# untitled.net
KiCad netlist of a schematic drawn in EAGLE
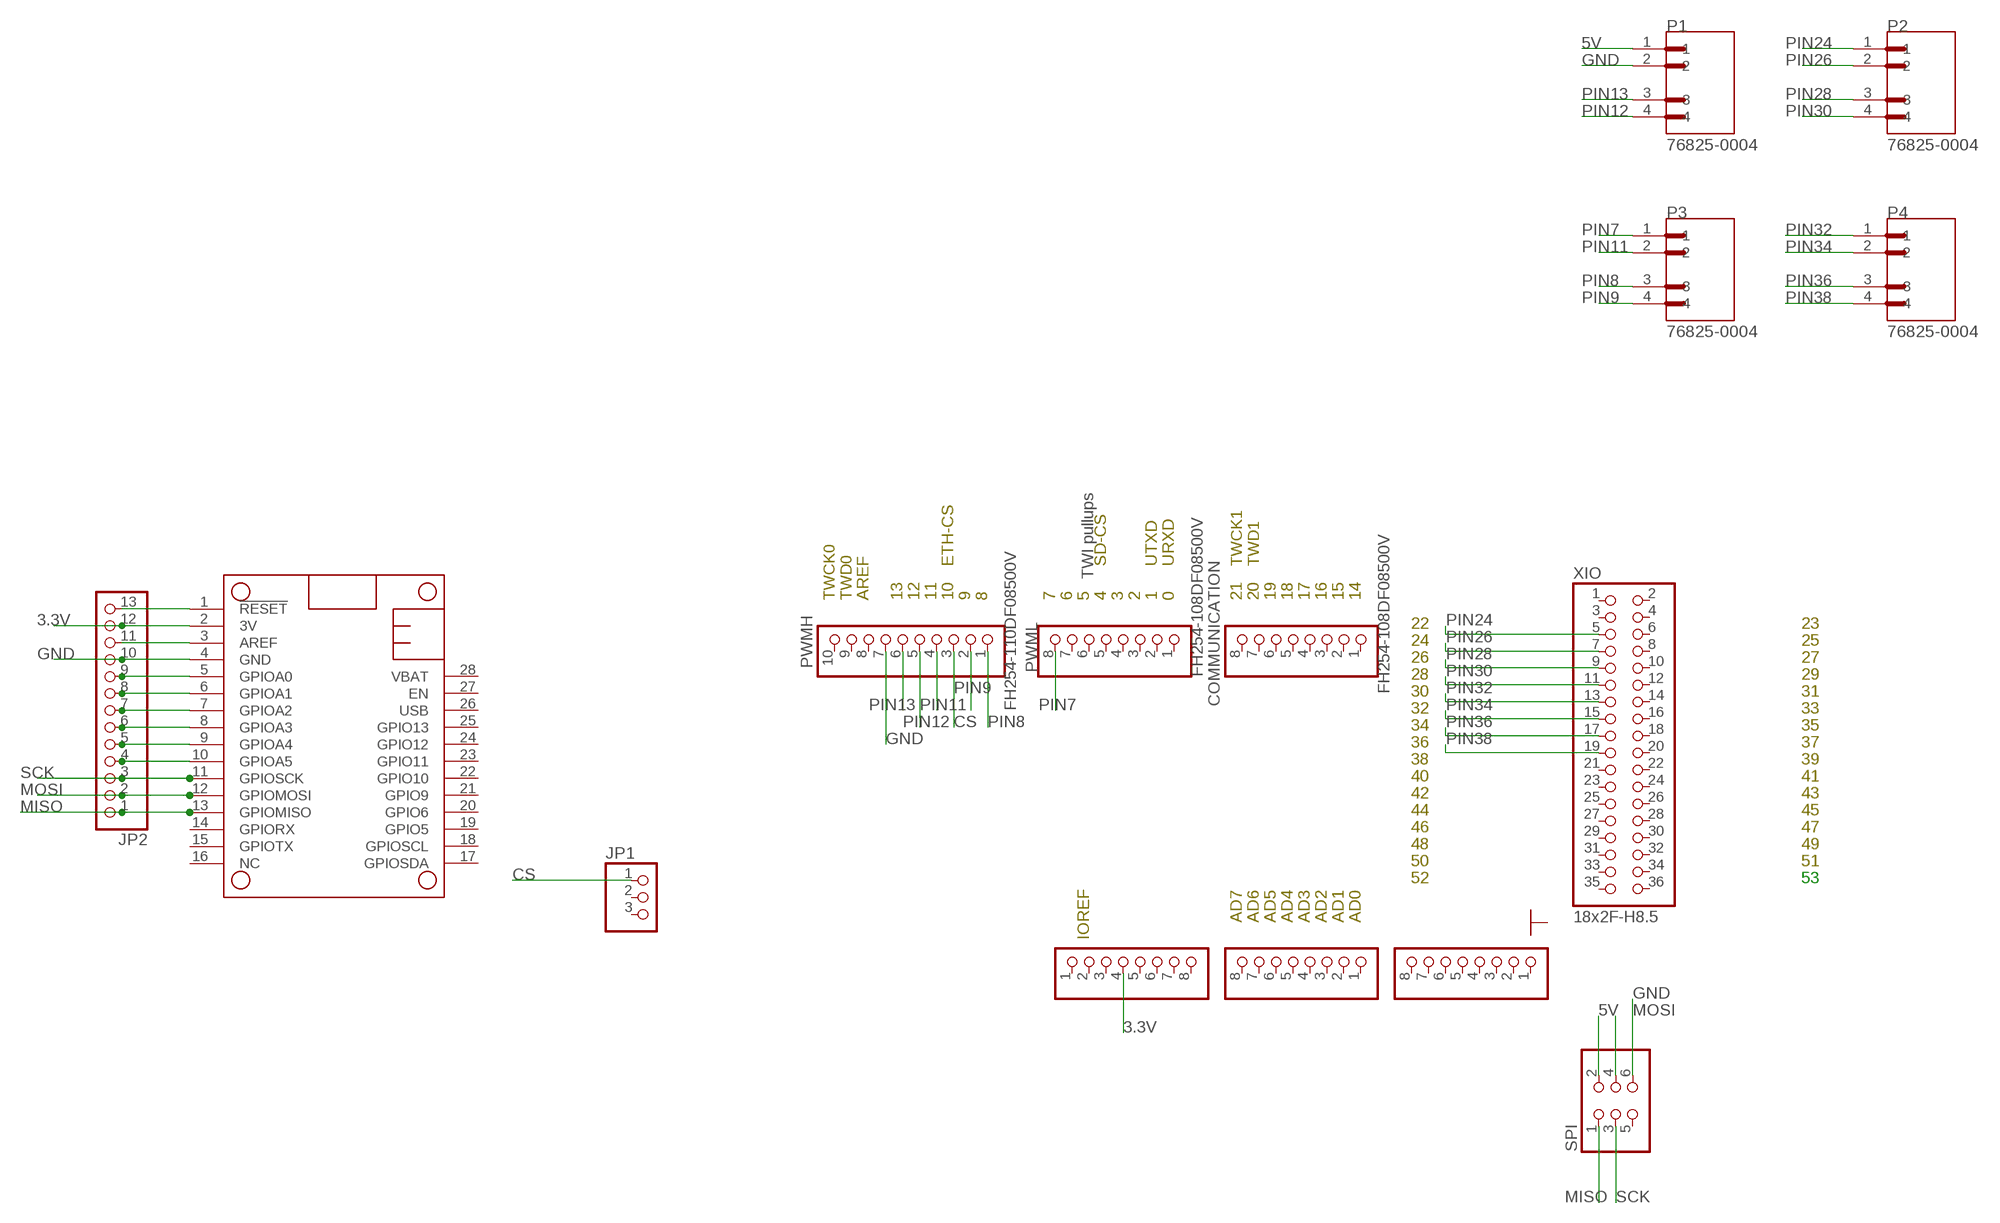
[diagram p0: schematic, sheet 1]

(export (version "E")
  (design (tool "Eeschema 10.0.6"))
  (components
    (comp (ref "ADCH")
      (value "FH254-108DF08500V")
      (footprint "eagle-import:1X08")
      (fields (field (name "PART_NUMBER") "20TW-536"))
      (libsource (lib "eagle-import") (part "1683_20TW-536"))
    )
    (comp (ref "ADCL")
      (value "FH254-108DF08500V")
      (footprint "eagle-import:1X08")
      (fields (field (name "PART_NUMBER") "20TW-536"))
      (libsource (lib "eagle-import") (part "1683_20TW-536"))
    )
    (comp (ref "COMMUNICATION")
      (value "FH254-108DF08500V")
      (footprint "eagle-import:1X08")
      (fields (field (name "PART_NUMBER") "20TW-536"))
      (libsource (lib "eagle-import") (part "1683_20TW-536"))
    )
    (comp (ref "JP1")
      (value "HEADER-1X376MIL")
      (footprint "eagle-import:1X03_ROUND_76")
      (libsource (lib "eagle-import") (part "HEADER-1X376MIL"))
    )
    (comp (ref "JP2")
      (value "HEADER-1X13")
      (footprint "eagle-import:1X13_ROUND_70")
      (libsource (lib "eagle-import") (part "HEADER-1X13"))
    )
    (comp (ref "MS1")
      (value "FEATHERWING_NODIM")
      (footprint "eagle-import:FEATHERWING_NODIM")
      (libsource (lib "eagle-import") (part "FEATHERWING_NODIM"))
    )
    (comp (ref "P1")
      (value "76825-0004")
      (footprint "eagle-import:MOLEX_76825-0004")
      (fields (field (name "MF") "Molex") (field (name "MP") "768250004"))
      (libsource (lib "eagle-import") (part "76825-0004"))
    )
    (comp (ref "P2")
      (value "76825-0004")
      (footprint "eagle-import:MOLEX_76825-0004")
      (fields (field (name "MF") "Molex") (field (name "MP") "768250004"))
      (libsource (lib "eagle-import") (part "76825-0004"))
    )
    (comp (ref "P3")
      (value "76825-0004")
      (footprint "eagle-import:MOLEX_76825-0004")
      (fields (field (name "MF") "Molex") (field (name "MP") "768250004"))
      (libsource (lib "eagle-import") (part "76825-0004"))
    )
    (comp (ref "P4")
      (value "76825-0004")
      (footprint "eagle-import:MOLEX_76825-0004")
      (fields (field (name "MF") "Molex") (field (name "MP") "768250004"))
      (libsource (lib "eagle-import") (part "76825-0004"))
    )
    (comp (ref "POWER")
      (value "FH254-108DF08500V")
      (footprint "eagle-import:1X08")
      (fields (field (name "PART_NUMBER") "20TW-536"))
      (libsource (lib "eagle-import") (part "1683_20TW-536"))
    )
    (comp (ref "PWMH")
      (value "FH254-110DF08500V")
      (footprint "eagle-import:1X10")
      (fields (field (name "PART_NUMBER") "20TW-537"))
      (libsource (lib "eagle-import") (part "1684_20TW-537"))
    )
    (comp (ref "PWML")
      (value "FH254-108DF08500V")
      (footprint "eagle-import:1X08")
      (fields (field (name "PART_NUMBER") "20TW-536"))
      (libsource (lib "eagle-import") (part "1683_20TW-536"))
    )
    (comp (ref "SPI")
      (value "ICSP")
      (footprint "eagle-import:2X03")
      (fields (field (name "PART_NUMBER") "PH254-203DF118A00V"))
      (libsource (lib "eagle-import") (part "0114_PH254-203DF118A00V"))
    )
    (comp (ref "XIO")
      (value "18x2F-H8.5")
      (footprint "eagle-import:2X18")
      (fields (field (name "PART_NUMBER") "12TW323"))
      (libsource (lib "eagle-import") (part "1756_12TW323"))
    )
  )
  (nets
    (net (code "1") (name "/3.3V") (class "Default")
      (node (ref "JP2") (pin "11") (pinfunction "11_11") (pintype "passive"))
      (node (ref "JP2") (pin "12") (pinfunction "12_12") (pintype "passive"))
      (node (ref "MS1") (pin "2") (pinfunction "3V_2") (pintype "power_in"))
      (node (ref "MS1") (pin "3") (pinfunction "AREF_3") (pintype "passive"))
      (node (ref "POWER") (pin "4") (pinfunction "4_4") (pintype "passive"))
    )
    (net (code "2") (name "/5V") (class "Default")
      (node (ref "P1") (pin "1") (pinfunction "1_1") (pintype "passive"))
      (node (ref "SPI") (pin "2") (pinfunction "2_2") (pintype "passive"))
    )
    (net (code "3") (name "/CS") (class "Default")
      (node (ref "JP1") (pin "1") (pinfunction "1_1") (pintype "passive"))
      (node (ref "PWMH") (pin "3") (pinfunction "3_3") (pintype "passive"))
    )
    (net (code "4") (name "/MISO") (class "Default")
      (node (ref "JP2") (pin "1") (pinfunction "1_1") (pintype "passive"))
      (node (ref "MS1") (pin "13") (pinfunction "GPIOMISO_13") (pintype "bidirectional"))
      (node (ref "SPI") (pin "1") (pinfunction "1_1") (pintype "passive"))
    )
    (net (code "5") (name "/MOSI") (class "Default")
      (node (ref "JP2") (pin "2") (pinfunction "2_2") (pintype "passive"))
      (node (ref "MS1") (pin "12") (pinfunction "GPIOMOSI_12") (pintype "bidirectional"))
      (node (ref "SPI") (pin "4") (pinfunction "4_4") (pintype "passive"))
    )
    (net (code "6") (name "/PIN7") (class "Default")
      (node (ref "P3") (pin "1") (pinfunction "1_1") (pintype "passive"))
      (node (ref "PWML") (pin "8") (pinfunction "8_8") (pintype "passive"))
    )
    (net (code "7") (name "/PIN8") (class "Default")
      (node (ref "P3") (pin "3") (pinfunction "3_3") (pintype "passive"))
      (node (ref "PWMH") (pin "1") (pinfunction "1_1") (pintype "passive"))
    )
    (net (code "8") (name "/PIN9") (class "Default")
      (node (ref "P3") (pin "4") (pinfunction "4_4") (pintype "passive"))
      (node (ref "PWMH") (pin "2") (pinfunction "2_2") (pintype "passive"))
    )
    (net (code "9") (name "/PIN11") (class "Default")
      (node (ref "P3") (pin "2") (pinfunction "2_2") (pintype "passive"))
      (node (ref "PWMH") (pin "4") (pinfunction "4_4") (pintype "passive"))
    )
    (net (code "10") (name "/PIN12") (class "Default")
      (node (ref "P1") (pin "4") (pinfunction "4_4") (pintype "passive"))
      (node (ref "PWMH") (pin "5") (pinfunction "5_5") (pintype "passive"))
    )
    (net (code "11") (name "/PIN13") (class "Default")
      (node (ref "P1") (pin "3") (pinfunction "3_3") (pintype "passive"))
      (node (ref "PWMH") (pin "6") (pinfunction "6_6") (pintype "passive"))
    )
    (net (code "12") (name "/PIN24") (class "Default")
      (node (ref "P2") (pin "1") (pinfunction "1_1") (pintype "passive"))
      (node (ref "XIO") (pin "5") (pinfunction "5_5") (pintype "passive"))
    )
    (net (code "13") (name "/PIN26") (class "Default")
      (node (ref "P2") (pin "2") (pinfunction "2_2") (pintype "passive"))
      (node (ref "XIO") (pin "7") (pinfunction "7_7") (pintype "passive"))
    )
    (net (code "14") (name "/PIN28") (class "Default")
      (node (ref "P2") (pin "3") (pinfunction "3_3") (pintype "passive"))
      (node (ref "XIO") (pin "9") (pinfunction "9_9") (pintype "passive"))
    )
    (net (code "15") (name "/PIN30") (class "Default")
      (node (ref "P2") (pin "4") (pinfunction "4_4") (pintype "passive"))
      (node (ref "XIO") (pin "11") (pinfunction "11_11") (pintype "passive"))
    )
    (net (code "16") (name "/PIN32") (class "Default")
      (node (ref "P4") (pin "1") (pinfunction "1_1") (pintype "passive"))
      (node (ref "XIO") (pin "13") (pinfunction "13_13") (pintype "passive"))
    )
    (net (code "17") (name "/PIN34") (class "Default")
      (node (ref "P4") (pin "2") (pinfunction "2_2") (pintype "passive"))
      (node (ref "XIO") (pin "15") (pinfunction "15_15") (pintype "passive"))
    )
    (net (code "18") (name "/PIN36") (class "Default")
      (node (ref "P4") (pin "3") (pinfunction "3_3") (pintype "passive"))
      (node (ref "XIO") (pin "17") (pinfunction "17_17") (pintype "passive"))
    )
    (net (code "19") (name "/PIN38") (class "Default")
      (node (ref "P4") (pin "4") (pinfunction "4_4") (pintype "passive"))
      (node (ref "XIO") (pin "19") (pinfunction "19_19") (pintype "passive"))
    )
    (net (code "20") (name "/SCK") (class "Default")
      (node (ref "JP2") (pin "3") (pinfunction "3_3") (pintype "passive"))
      (node (ref "MS1") (pin "11") (pinfunction "GPIOSCK_11") (pintype "bidirectional"))
      (node (ref "SPI") (pin "3") (pinfunction "3_3") (pintype "passive"))
    )
    (net (code "21") (name "/USB") (class "Default")
      (node (ref "MS1") (pin "26") (pinfunction "USB_26") (pintype "power_in"))
    )
    (net (code "22") (name "/VBAT") (class "Default")
      (node (ref "MS1") (pin "28") (pinfunction "VBAT_28") (pintype "power_in"))
    )
    (net (code "23") (name "GND") (class "Default")
      (node (ref "JP2") (pin "10") (pinfunction "10_10") (pintype "passive"))
      (node (ref "MS1") (pin "4") (pinfunction "GND_4") (pintype "power_in"))
      (node (ref "P1") (pin "2") (pinfunction "2_2") (pintype "passive"))
      (node (ref "PWMH") (pin "7") (pinfunction "7_7") (pintype "passive"))
      (node (ref "SPI") (pin "6") (pinfunction "6_6") (pintype "passive"))
    )
    (net (code "24") (name "Net-(MS1-GPIOA0)") (class "Default")
      (node (ref "JP2") (pin "9") (pinfunction "9_9") (pintype "passive"))
      (node (ref "MS1") (pin "5") (pinfunction "GPIOA0_5") (pintype "bidirectional"))
    )
    (net (code "25") (name "Net-(MS1-GPIOA1)") (class "Default")
      (node (ref "JP2") (pin "8") (pinfunction "8_8") (pintype "passive"))
      (node (ref "MS1") (pin "6") (pinfunction "GPIOA1_6") (pintype "bidirectional"))
    )
    (net (code "26") (name "Net-(MS1-GPIOA2)") (class "Default")
      (node (ref "JP2") (pin "7") (pinfunction "7_7") (pintype "passive"))
      (node (ref "MS1") (pin "7") (pinfunction "GPIOA2_7") (pintype "bidirectional"))
    )
    (net (code "27") (name "Net-(MS1-GPIOA3)") (class "Default")
      (node (ref "JP2") (pin "6") (pinfunction "6_6") (pintype "passive"))
      (node (ref "MS1") (pin "8") (pinfunction "GPIOA3_8") (pintype "bidirectional"))
    )
    (net (code "28") (name "Net-(MS1-GPIOA4)") (class "Default")
      (node (ref "JP2") (pin "5") (pinfunction "5_5") (pintype "passive"))
      (node (ref "MS1") (pin "9") (pinfunction "GPIOA4_9") (pintype "bidirectional"))
    )
    (net (code "29") (name "Net-(MS1-GPIOA5)") (class "Default")
      (node (ref "JP2") (pin "4") (pinfunction "4_4") (pintype "passive"))
      (node (ref "MS1") (pin "10") (pinfunction "GPIOA5_10") (pintype "bidirectional"))
    )
    (net (code "30") (name "Net-(MS1-~{RESET})") (class "Default")
      (node (ref "JP2") (pin "13") (pinfunction "13_13") (pintype "passive"))
      (node (ref "MS1") (pin "1") (pinfunction "~{RESET}_1") (pintype "input"))
    )
    (net (code "31") (name "unconnected-(ADCH-Pad1)") (class "Default")
      (node (ref "ADCH") (pin "1") (pinfunction "1_1") (pintype "passive"))
    )
    (net (code "32") (name "unconnected-(ADCH-Pad2)") (class "Default")
      (node (ref "ADCH") (pin "2") (pinfunction "2_2") (pintype "passive"))
    )
    (net (code "33") (name "unconnected-(ADCH-Pad3)") (class "Default")
      (node (ref "ADCH") (pin "3") (pinfunction "3_3") (pintype "passive"))
    )
    (net (code "34") (name "unconnected-(ADCH-Pad4)") (class "Default")
      (node (ref "ADCH") (pin "4") (pinfunction "4_4") (pintype "passive"))
    )
    (net (code "35") (name "unconnected-(ADCH-Pad5)") (class "Default")
      (node (ref "ADCH") (pin "5") (pinfunction "5_5") (pintype "passive"))
    )
    (net (code "36") (name "unconnected-(ADCH-Pad6)") (class "Default")
      (node (ref "ADCH") (pin "6") (pinfunction "6_6") (pintype "passive"))
    )
    (net (code "37") (name "unconnected-(ADCH-Pad7)") (class "Default")
      (node (ref "ADCH") (pin "7") (pinfunction "7_7") (pintype "passive"))
    )
    (net (code "38") (name "unconnected-(ADCH-Pad8)") (class "Default")
      (node (ref "ADCH") (pin "8") (pinfunction "8_8") (pintype "passive"))
    )
    (net (code "39") (name "unconnected-(ADCL-Pad1)") (class "Default")
      (node (ref "ADCL") (pin "1") (pinfunction "1_1") (pintype "passive"))
    )
    (net (code "40") (name "unconnected-(ADCL-Pad2)") (class "Default")
      (node (ref "ADCL") (pin "2") (pinfunction "2_2") (pintype "passive"))
    )
    (net (code "41") (name "unconnected-(ADCL-Pad3)") (class "Default")
      (node (ref "ADCL") (pin "3") (pinfunction "3_3") (pintype "passive"))
    )
    (net (code "42") (name "unconnected-(ADCL-Pad4)") (class "Default")
      (node (ref "ADCL") (pin "4") (pinfunction "4_4") (pintype "passive"))
    )
    (net (code "43") (name "unconnected-(ADCL-Pad5)") (class "Default")
      (node (ref "ADCL") (pin "5") (pinfunction "5_5") (pintype "passive"))
    )
    (net (code "44") (name "unconnected-(ADCL-Pad6)") (class "Default")
      (node (ref "ADCL") (pin "6") (pinfunction "6_6") (pintype "passive"))
    )
    (net (code "45") (name "unconnected-(ADCL-Pad7)") (class "Default")
      (node (ref "ADCL") (pin "7") (pinfunction "7_7") (pintype "passive"))
    )
    (net (code "46") (name "unconnected-(ADCL-Pad8)") (class "Default")
      (node (ref "ADCL") (pin "8") (pinfunction "8_8") (pintype "passive"))
    )
    (net (code "47") (name "unconnected-(COMMUNICATION-Pad1)") (class "Default")
      (node (ref "COMMUNICATION") (pin "1") (pinfunction "1_1") (pintype "passive"))
    )
    (net (code "48") (name "unconnected-(COMMUNICATION-Pad2)") (class "Default")
      (node (ref "COMMUNICATION") (pin "2") (pinfunction "2_2") (pintype "passive"))
    )
    (net (code "49") (name "unconnected-(COMMUNICATION-Pad3)") (class "Default")
      (node (ref "COMMUNICATION") (pin "3") (pinfunction "3_3") (pintype "passive"))
    )
    (net (code "50") (name "unconnected-(COMMUNICATION-Pad4)") (class "Default")
      (node (ref "COMMUNICATION") (pin "4") (pinfunction "4_4") (pintype "passive"))
    )
    (net (code "51") (name "unconnected-(COMMUNICATION-Pad5)") (class "Default")
      (node (ref "COMMUNICATION") (pin "5") (pinfunction "5_5") (pintype "passive"))
    )
    (net (code "52") (name "unconnected-(COMMUNICATION-Pad6)") (class "Default")
      (node (ref "COMMUNICATION") (pin "6") (pinfunction "6_6") (pintype "passive"))
    )
    (net (code "53") (name "unconnected-(COMMUNICATION-Pad7)") (class "Default")
      (node (ref "COMMUNICATION") (pin "7") (pinfunction "7_7") (pintype "passive"))
    )
    (net (code "54") (name "unconnected-(COMMUNICATION-Pad8)") (class "Default")
      (node (ref "COMMUNICATION") (pin "8") (pinfunction "8_8") (pintype "passive"))
    )
    (net (code "55") (name "unconnected-(JP1-Pad2)") (class "Default")
      (node (ref "JP1") (pin "2") (pinfunction "2_2") (pintype "passive"))
    )
    (net (code "56") (name "unconnected-(JP1-Pad3)") (class "Default")
      (node (ref "JP1") (pin "3") (pinfunction "3_3") (pintype "passive"))
    )
    (net (code "57") (name "unconnected-(MS1-EN-Pad27)") (class "Default")
      (node (ref "MS1") (pin "27") (pinfunction "EN_27") (pintype "passive"))
    )
    (net (code "58") (name "unconnected-(MS1-GPIO5-Pad19)") (class "Default")
      (node (ref "MS1") (pin "19") (pinfunction "GPIO5_19") (pintype "bidirectional"))
    )
    (net (code "59") (name "unconnected-(MS1-GPIO6-Pad20)") (class "Default")
      (node (ref "MS1") (pin "20") (pinfunction "GPIO6_20") (pintype "bidirectional"))
    )
    (net (code "60") (name "unconnected-(MS1-GPIO9-Pad21)") (class "Default")
      (node (ref "MS1") (pin "21") (pinfunction "GPIO9_21") (pintype "bidirectional"))
    )
    (net (code "61") (name "unconnected-(MS1-GPIO10-Pad22)") (class "Default")
      (node (ref "MS1") (pin "22") (pinfunction "GPIO10_22") (pintype "bidirectional"))
    )
    (net (code "62") (name "unconnected-(MS1-GPIO11-Pad23)") (class "Default")
      (node (ref "MS1") (pin "23") (pinfunction "GPIO11_23") (pintype "bidirectional"))
    )
    (net (code "63") (name "unconnected-(MS1-GPIO12-Pad24)") (class "Default")
      (node (ref "MS1") (pin "24") (pinfunction "GPIO12_24") (pintype "bidirectional"))
    )
    (net (code "64") (name "unconnected-(MS1-GPIO13-Pad25)") (class "Default")
      (node (ref "MS1") (pin "25") (pinfunction "GPIO13_25") (pintype "bidirectional"))
    )
    (net (code "65") (name "unconnected-(MS1-GPIORX-Pad14)") (class "Default")
      (node (ref "MS1") (pin "14") (pinfunction "GPIORX_14") (pintype "bidirectional"))
    )
    (net (code "66") (name "unconnected-(MS1-GPIOSCL-Pad18)") (class "Default")
      (node (ref "MS1") (pin "18") (pinfunction "GPIOSCL_18") (pintype "bidirectional"))
    )
    (net (code "67") (name "unconnected-(MS1-GPIOSDA-Pad17)") (class "Default")
      (node (ref "MS1") (pin "17") (pinfunction "GPIOSDA_17") (pintype "bidirectional"))
    )
    (net (code "68") (name "unconnected-(MS1-GPIOTX-Pad15)") (class "Default")
      (node (ref "MS1") (pin "15") (pinfunction "GPIOTX_15") (pintype "bidirectional"))
    )
    (net (code "69") (name "unconnected-(MS1-NC-Pad16)") (class "Default")
      (node (ref "MS1") (pin "16") (pinfunction "NC_16") (pintype "passive"))
    )
    (net (code "70") (name "unconnected-(POWER-Pad1)") (class "Default")
      (node (ref "POWER") (pin "1") (pinfunction "1_1") (pintype "passive"))
    )
    (net (code "71") (name "unconnected-(POWER-Pad2)") (class "Default")
      (node (ref "POWER") (pin "2") (pinfunction "2_2") (pintype "passive"))
    )
    (net (code "72") (name "unconnected-(POWER-Pad3)") (class "Default")
      (node (ref "POWER") (pin "3") (pinfunction "3_3") (pintype "passive"))
    )
    (net (code "73") (name "unconnected-(POWER-Pad5)") (class "Default")
      (node (ref "POWER") (pin "5") (pinfunction "5_5") (pintype "passive"))
    )
    (net (code "74") (name "unconnected-(POWER-Pad6)") (class "Default")
      (node (ref "POWER") (pin "6") (pinfunction "6_6") (pintype "passive"))
    )
    (net (code "75") (name "unconnected-(POWER-Pad7)") (class "Default")
      (node (ref "POWER") (pin "7") (pinfunction "7_7") (pintype "passive"))
    )
    (net (code "76") (name "unconnected-(POWER-Pad8)") (class "Default")
      (node (ref "POWER") (pin "8") (pinfunction "8_8") (pintype "passive"))
    )
    (net (code "77") (name "unconnected-(PWMH-Pad8)") (class "Default")
      (node (ref "PWMH") (pin "8") (pinfunction "8_8") (pintype "passive"))
    )
    (net (code "78") (name "unconnected-(PWMH-Pad9)") (class "Default")
      (node (ref "PWMH") (pin "9") (pinfunction "9_9") (pintype "passive"))
    )
    (net (code "79") (name "unconnected-(PWMH-Pad10)") (class "Default")
      (node (ref "PWMH") (pin "10") (pinfunction "10_10") (pintype "passive"))
    )
    (net (code "80") (name "unconnected-(PWML-Pad1)") (class "Default")
      (node (ref "PWML") (pin "1") (pinfunction "1_1") (pintype "passive"))
    )
    (net (code "81") (name "unconnected-(PWML-Pad2)") (class "Default")
      (node (ref "PWML") (pin "2") (pinfunction "2_2") (pintype "passive"))
    )
    (net (code "82") (name "unconnected-(PWML-Pad3)") (class "Default")
      (node (ref "PWML") (pin "3") (pinfunction "3_3") (pintype "passive"))
    )
    (net (code "83") (name "unconnected-(PWML-Pad4)") (class "Default")
      (node (ref "PWML") (pin "4") (pinfunction "4_4") (pintype "passive"))
    )
    (net (code "84") (name "unconnected-(PWML-Pad5)") (class "Default")
      (node (ref "PWML") (pin "5") (pinfunction "5_5") (pintype "passive"))
    )
    (net (code "85") (name "unconnected-(PWML-Pad6)") (class "Default")
      (node (ref "PWML") (pin "6") (pinfunction "6_6") (pintype "passive"))
    )
    (net (code "86") (name "unconnected-(PWML-Pad7)") (class "Default")
      (node (ref "PWML") (pin "7") (pinfunction "7_7") (pintype "passive"))
    )
    (net (code "87") (name "unconnected-(SPI-Pad5)") (class "Default")
      (node (ref "SPI") (pin "5") (pinfunction "5_5") (pintype "passive"))
    )
    (net (code "88") (name "unconnected-(XIO-Pad1)") (class "Default")
      (node (ref "XIO") (pin "1") (pinfunction "1_1") (pintype "passive"))
    )
    (net (code "89") (name "unconnected-(XIO-Pad2)") (class "Default")
      (node (ref "XIO") (pin "2") (pinfunction "2_2") (pintype "passive"))
    )
    (net (code "90") (name "unconnected-(XIO-Pad3)") (class "Default")
      (node (ref "XIO") (pin "3") (pinfunction "3_3") (pintype "passive"))
    )
    (net (code "91") (name "unconnected-(XIO-Pad4)") (class "Default")
      (node (ref "XIO") (pin "4") (pinfunction "4_4") (pintype "passive"))
    )
    (net (code "92") (name "unconnected-(XIO-Pad6)") (class "Default")
      (node (ref "XIO") (pin "6") (pinfunction "6_6") (pintype "passive"))
    )
    (net (code "93") (name "unconnected-(XIO-Pad8)") (class "Default")
      (node (ref "XIO") (pin "8") (pinfunction "8_8") (pintype "passive"))
    )
    (net (code "94") (name "unconnected-(XIO-Pad10)") (class "Default")
      (node (ref "XIO") (pin "10") (pinfunction "10_10") (pintype "passive"))
    )
    (net (code "95") (name "unconnected-(XIO-Pad12)") (class "Default")
      (node (ref "XIO") (pin "12") (pinfunction "12_12") (pintype "passive"))
    )
    (net (code "96") (name "unconnected-(XIO-Pad14)") (class "Default")
      (node (ref "XIO") (pin "14") (pinfunction "14_14") (pintype "passive"))
    )
    (net (code "97") (name "unconnected-(XIO-Pad16)") (class "Default")
      (node (ref "XIO") (pin "16") (pinfunction "16_16") (pintype "passive"))
    )
    (net (code "98") (name "unconnected-(XIO-Pad18)") (class "Default")
      (node (ref "XIO") (pin "18") (pinfunction "18_18") (pintype "passive"))
    )
    (net (code "99") (name "unconnected-(XIO-Pad20)") (class "Default")
      (node (ref "XIO") (pin "20") (pinfunction "20_20") (pintype "passive"))
    )
    (net (code "100") (name "unconnected-(XIO-Pad21)") (class "Default")
      (node (ref "XIO") (pin "21") (pinfunction "21_21") (pintype "passive"))
    )
    (net (code "101") (name "unconnected-(XIO-Pad22)") (class "Default")
      (node (ref "XIO") (pin "22") (pinfunction "22_22") (pintype "passive"))
    )
    (net (code "102") (name "unconnected-(XIO-Pad23)") (class "Default")
      (node (ref "XIO") (pin "23") (pinfunction "23_23") (pintype "passive"))
    )
    (net (code "103") (name "unconnected-(XIO-Pad24)") (class "Default")
      (node (ref "XIO") (pin "24") (pinfunction "24_24") (pintype "passive"))
    )
    (net (code "104") (name "unconnected-(XIO-Pad25)") (class "Default")
      (node (ref "XIO") (pin "25") (pinfunction "25_25") (pintype "passive"))
    )
    (net (code "105") (name "unconnected-(XIO-Pad26)") (class "Default")
      (node (ref "XIO") (pin "26") (pinfunction "26_26") (pintype "passive"))
    )
    (net (code "106") (name "unconnected-(XIO-Pad27)") (class "Default")
      (node (ref "XIO") (pin "27") (pinfunction "27_27") (pintype "passive"))
    )
    (net (code "107") (name "unconnected-(XIO-Pad28)") (class "Default")
      (node (ref "XIO") (pin "28") (pinfunction "28_28") (pintype "passive"))
    )
    (net (code "108") (name "unconnected-(XIO-Pad29)") (class "Default")
      (node (ref "XIO") (pin "29") (pinfunction "29_29") (pintype "passive"))
    )
    (net (code "109") (name "unconnected-(XIO-Pad30)") (class "Default")
      (node (ref "XIO") (pin "30") (pinfunction "30_30") (pintype "passive"))
    )
    (net (code "110") (name "unconnected-(XIO-Pad31)") (class "Default")
      (node (ref "XIO") (pin "31") (pinfunction "31_31") (pintype "passive"))
    )
    (net (code "111") (name "unconnected-(XIO-Pad32)") (class "Default")
      (node (ref "XIO") (pin "32") (pinfunction "32_32") (pintype "passive"))
    )
    (net (code "112") (name "unconnected-(XIO-Pad33)") (class "Default")
      (node (ref "XIO") (pin "33") (pinfunction "33_33") (pintype "passive"))
    )
    (net (code "113") (name "unconnected-(XIO-Pad34)") (class "Default")
      (node (ref "XIO") (pin "34") (pinfunction "34_34") (pintype "passive"))
    )
    (net (code "114") (name "unconnected-(XIO-Pad35)") (class "Default")
      (node (ref "XIO") (pin "35") (pinfunction "35_35") (pintype "passive"))
    )
    (net (code "115") (name "unconnected-(XIO-Pad36)") (class "Default")
      (node (ref "XIO") (pin "36") (pinfunction "36_36") (pintype "passive"))
    )
  )
)
